# SCH_Stepper-Relay-V2_2024-11-13.net
KiCad netlist of a schematic drawn in EasyEDA
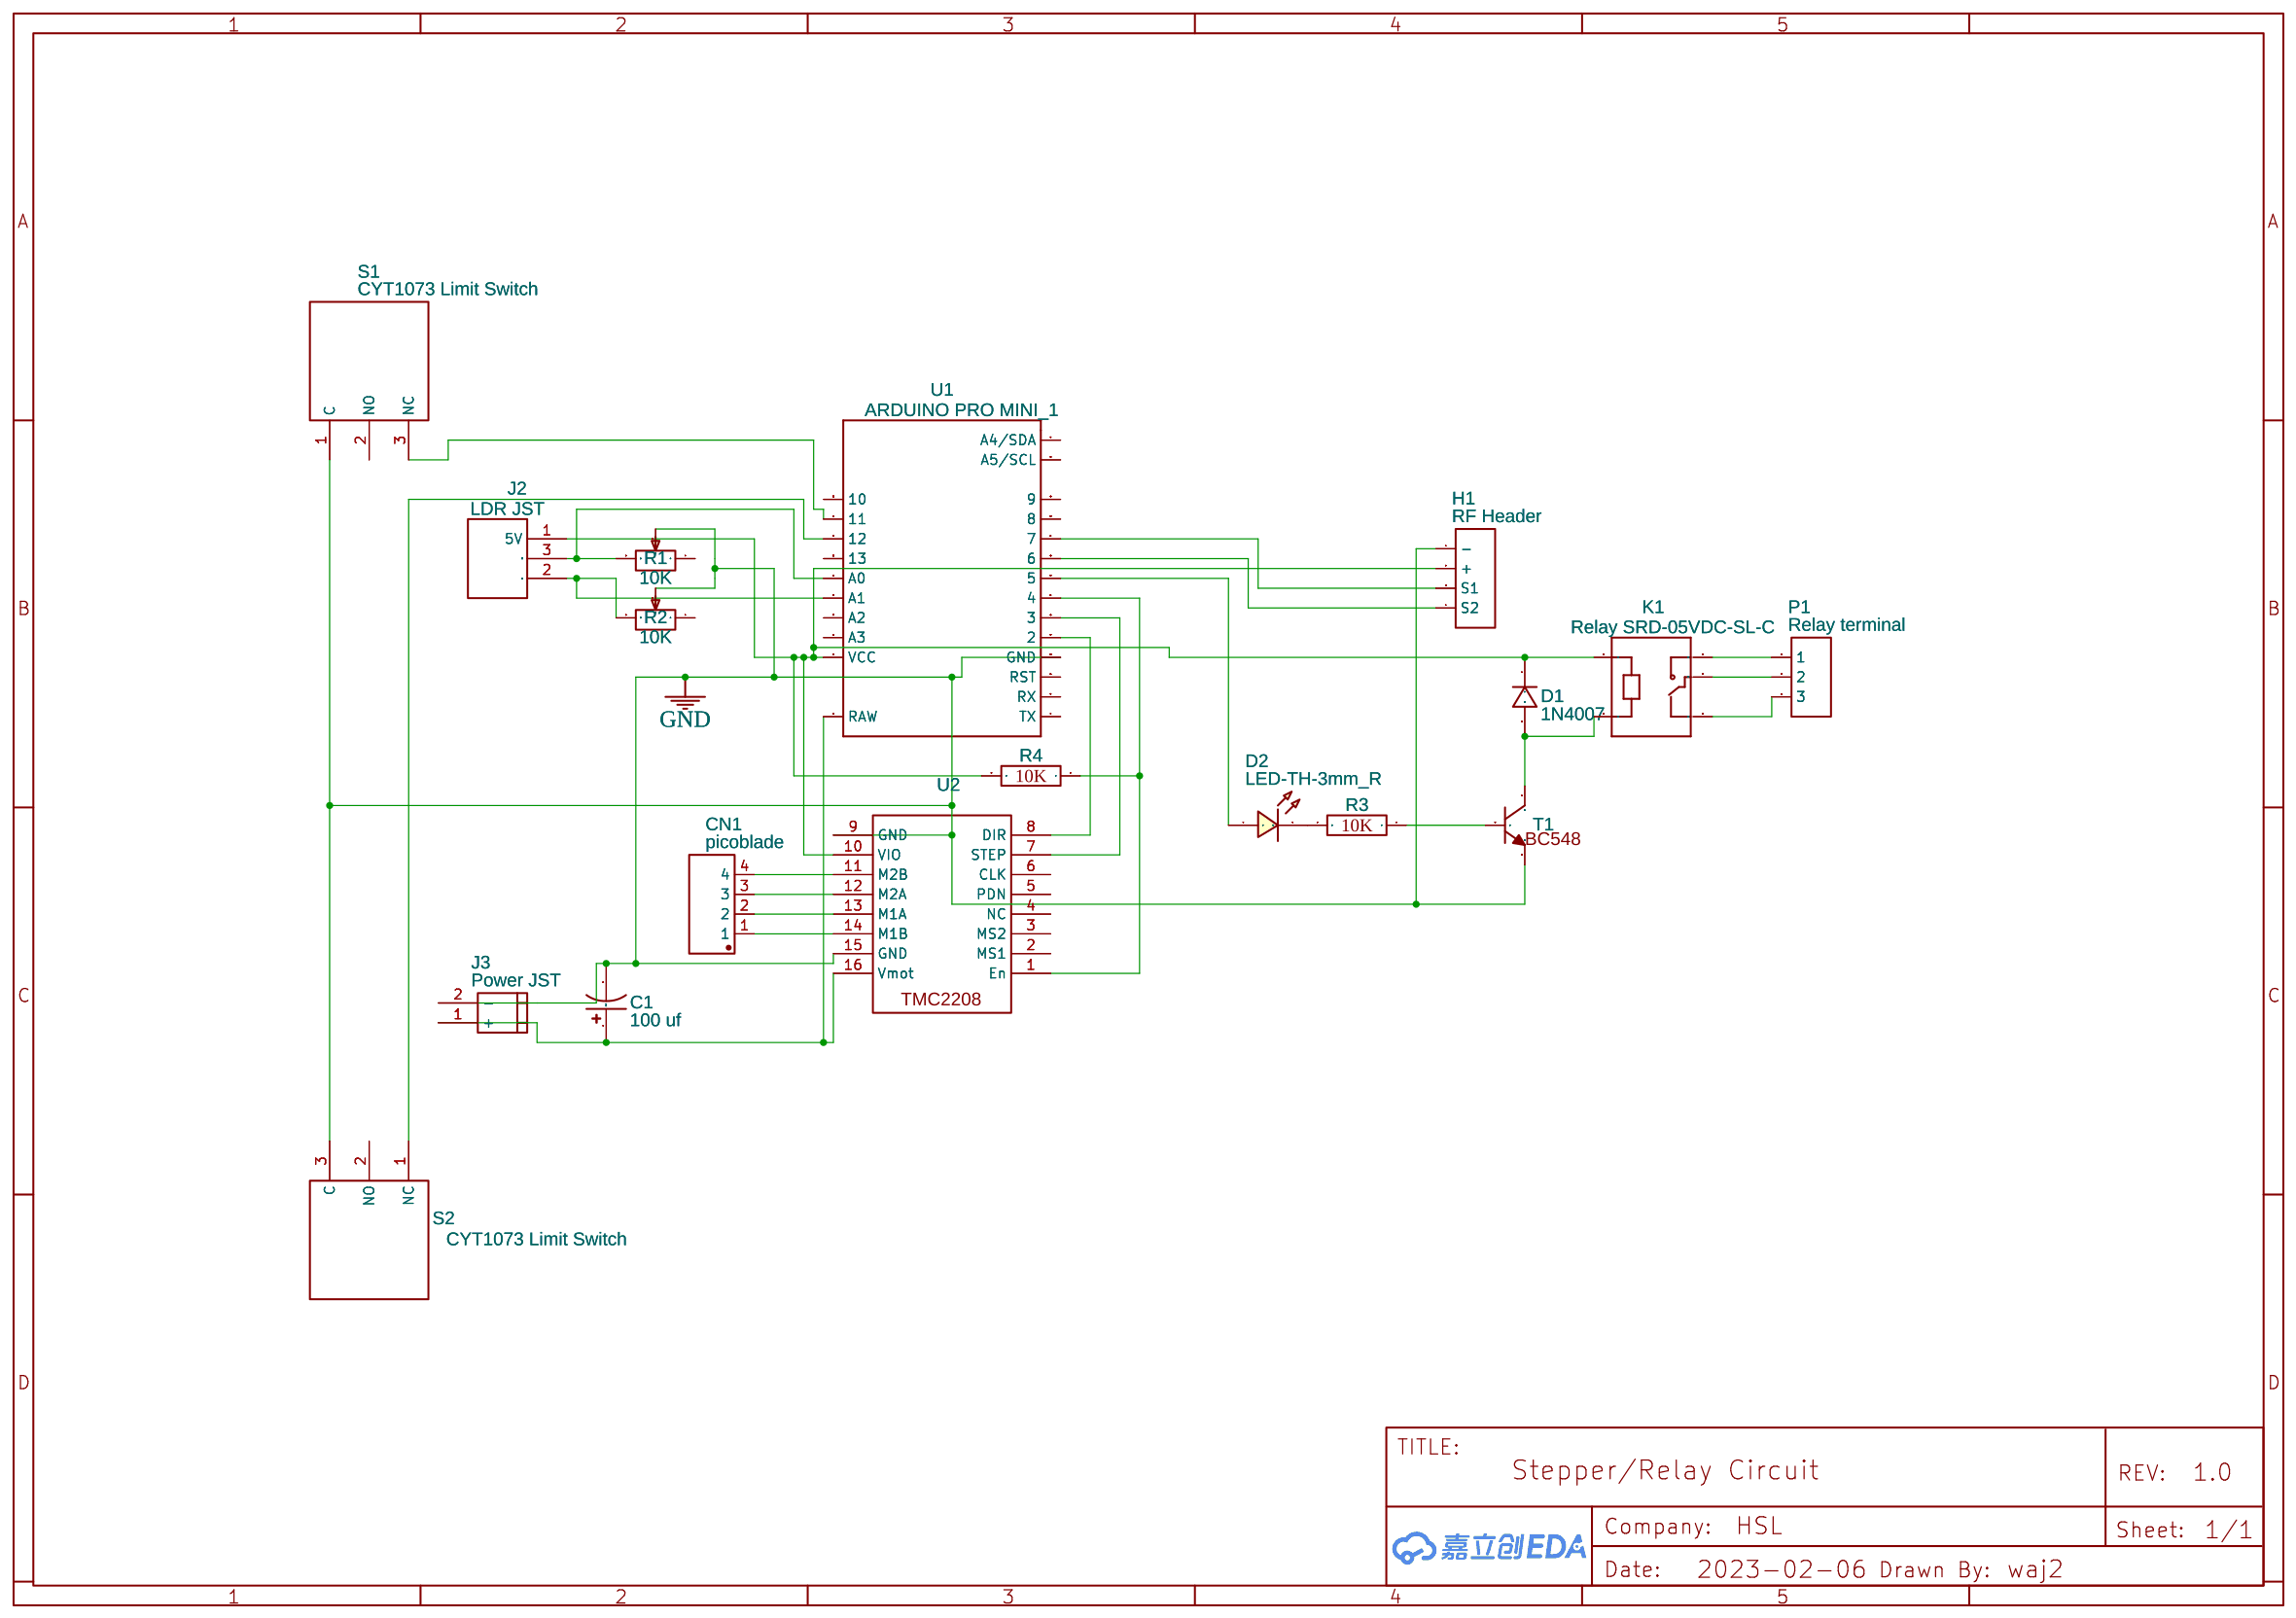
[diagram p0: schematic sheet]

(export (version "E")
  (design (tool "Eeschema 10.0.6"))
  (components
    (comp (ref "C1") (value "100 uf") (libsource (lib "") (part "CE_TH_D6.3×F2.5_US")))
    (comp (ref "CN1")
      (value "picoblade")
      (fields (field (name "Manufacturer Part") "0530474310") (field (name "Manufacturer") "MOLEX"))
      (libsource (lib "") (part "MOLEX_0530470410"))
    )
    (comp (ref "D1")
      (value "1N4007")
      (fields (field (name "Manufacturer") "SEMTECH"))
      (libsource (lib "") (part "1N4007"))
    )
    (comp (ref "D2")
      (value "LED-TH-3mm_R")
      (fields
        (field (name "Manufacturer Part") "204-10SDRD/S530-A3-L")
        (field (name "Manufacturer") "EVERLIGHT(台湾亿光)")
      )
      (libsource (lib "") (part "LED-TH-3mm_R"))
    )
    (comp (ref "H1") (value "RF Header") (libsource (lib "") (part "HDR-F-2.54_1x4")))
    (comp (ref "J2")
      (value "LDR JST")
      (fields (field (name "Manufacturer Part") "JST-5-PTH"))
      (libsource (lib "") (part "JST-HX 3P RIGHT ANGLE COPY"))
    )
    (comp (ref "J3")
      (value "Power JST")
      (fields (field (name "Manufacturer Part") "XH-2PWB") (field (name "Manufacturer") "ReliaPro"))
      (libsource (lib "") (part "XH-2PWB"))
    )
    (comp (ref "K1")
      (value "Relay SRD-05VDC-SL-C")
      (libsource (lib "") (part "SRD-05VDC-SL-C_SRD-05VDC-SL-C"))
    )
    (comp (ref "P1") (value "Relay terminal") (libsource (lib "") (part "CONN-TH_3P-P5.00")))
    (comp (ref "R1")
      (value "10K")
      (fields (field (name "Manufacturer Part") "RM065-V1-5K blue") (field (name "Manufacturer") "ReliaPro"))
      (libsource (lib "") (part "TRIMPOT RM065"))
    )
    (comp (ref "R2")
      (value "10K")
      (fields (field (name "Manufacturer Part") "RM065-V1-5K blue") (field (name "Manufacturer") "ReliaPro"))
      (libsource (lib "") (part "TRIMPOT RM065"))
    )
    (comp (ref "R3") (value "RESISTOR 10K") (libsource (lib "") (part "RESISTOR 10K")))
    (comp (ref "R4") (value "RESISTOR 10K") (libsource (lib "") (part "RESISTOR 10K")))
    (comp (ref "S1")
      (value "CYT1073 Limit Switch")
      (fields (field (name "Manufacturer Part") "Cylewet"))
      (libsource (lib "") (part "CYT1073 Limit Switch"))
    )
    (comp (ref "S2")
      (value "CYT1073 Limit Switch")
      (fields (field (name "Manufacturer Part") "Cylewet"))
      (libsource (lib "") (part "CYT1073 Limit Switch_1"))
    )
    (comp (ref "T1") (value "BC548") (libsource (lib "") (part "BC548")))
    (comp (ref "U1") (value "ARDUINO PRO MINI_1") (libsource (lib "") (part "ARDUINO PRO MINI_1")))
    (comp (ref "U2") (value "U2") (libsource (lib "") (part "ТМС2208v1.0")))
  )
  (nets
    (net (code "1") (name "GND") (class "Default")
      (node (ref "C1") (pin "2") (pinfunction "2_2") (pintype "unspecified"))
      (node (ref "H1") (pin "1") (pinfunction "-_1") (pintype "unspecified"))
      (node (ref "J3") (pin "2") (pinfunction "-_2") (pintype "unspecified"))
      (node (ref "R1") (pin "2") (pinfunction "2_2") (pintype "input"))
      (node (ref "R2") (pin "2") (pinfunction "2_2") (pintype "input"))
      (node (ref "S1") (pin "1") (pinfunction "C_1") (pintype "unspecified"))
      (node (ref "S2") (pin "3") (pinfunction "C_3") (pintype "unspecified"))
      (node (ref "T1") (pin "3") (pinfunction "E_3") (pintype "unspecified"))
      (node (ref "U1") (pin "GND") (pinfunction "GND_GND") (pintype "unspecified"))
      (node (ref "U2") (pin "15") (pinfunction "GND_15") (pintype "unspecified"))
      (node (ref "U2") (pin "9") (pinfunction "GND_9") (pintype "unspecified"))
    )
    (net (code "2") (name "Net-(D2-Pad2)") (class "Default")
      (node (ref "D2") (pin "2") (pinfunction "2_2") (pintype "unspecified"))
      (node (ref "R3") (pin "2") (pinfunction "2_2") (pintype "unspecified"))
    )
    (net (code "3") (name "Net-(H1-+)") (class "Default")
      (node (ref "D1") (pin "1") (pinfunction "1_1") (pintype "unspecified"))
      (node (ref "H1") (pin "2") (pinfunction "+_2") (pintype "unspecified"))
      (node (ref "J2") (pin "1") (pinfunction "5V_1") (pintype "unspecified"))
      (node (ref "K1") (pin "A1") (pinfunction "A1_A1") (pintype "bidirectional"))
      (node (ref "R4") (pin "2") (pinfunction "2_2") (pintype "unspecified"))
      (node (ref "U1") (pin "VCC") (pinfunction "VCC_VCC") (pintype "unspecified"))
      (node (ref "U2") (pin "10") (pinfunction "VIO_10") (pintype "unspecified"))
    )
    (net (code "4") (name "Net-(H1-S1)") (class "Default")
      (node (ref "H1") (pin "3") (pinfunction "S1_3") (pintype "unspecified"))
      (node (ref "U1") (pin "D7") (pinfunction "7_D7") (pintype "unspecified"))
    )
    (net (code "5") (name "Net-(H1-S2)") (class "Default")
      (node (ref "H1") (pin "4") (pinfunction "S2_4") (pintype "unspecified"))
      (node (ref "U1") (pin "D6") (pinfunction "6_D6") (pintype "unspecified"))
    )
    (net (code "6") (name "Net-(J2-S1)") (class "Default")
      (node (ref "J2") (pin "2") (pinfunction "S1_2") (pintype "unspecified"))
      (node (ref "R2") (pin "3") (pinfunction "3_3") (pintype "input"))
      (node (ref "U1") (pin "A1") (pinfunction "A1_A1") (pintype "unspecified"))
    )
    (net (code "7") (name "Net-(J2-S2)") (class "Default")
      (node (ref "J2") (pin "3") (pinfunction "S2_3") (pintype "unspecified"))
      (node (ref "R1") (pin "3") (pinfunction "3_3") (pintype "input"))
      (node (ref "U1") (pin "A0") (pinfunction "A0_A0") (pintype "unspecified"))
    )
    (net (code "8") (name "Net-(J3-+)") (class "Default")
      (node (ref "C1") (pin "1") (pinfunction "1_1") (pintype "unspecified"))
      (node (ref "J3") (pin "1") (pinfunction "+_1") (pintype "unspecified"))
      (node (ref "U1") (pin "RAW") (pinfunction "RAW_RAW") (pintype "unspecified"))
      (node (ref "U2") (pin "16") (pinfunction "Vmot_16") (pintype "unspecified"))
    )
    (net (code "9") (name "Net-(K1-PadCOM)") (class "Default")
      (node (ref "K1") (pin "COM") (pinfunction "COM_COM") (pintype "bidirectional"))
      (node (ref "P1") (pin "2") (pinfunction "2_2") (pintype "unspecified"))
    )
    (net (code "10") (name "Net-(K1-PadNC)") (class "Default")
      (node (ref "K1") (pin "NC") (pinfunction "NC_NC") (pintype "bidirectional"))
      (node (ref "P1") (pin "3") (pinfunction "3_3") (pintype "unspecified"))
    )
    (net (code "11") (name "Net-(K1-PadNO)") (class "Default")
      (node (ref "K1") (pin "NO") (pinfunction "NO_NO") (pintype "bidirectional"))
      (node (ref "P1") (pin "1") (pinfunction "1_1") (pintype "unspecified"))
    )
    (net (code "12") (name "Net-(S1-NC)") (class "Default")
      (node (ref "S1") (pin "3") (pinfunction "NC_3") (pintype "unspecified"))
      (node (ref "U1") (pin "D11") (pinfunction "11_D11") (pintype "unspecified"))
    )
    (net (code "13") (name "Net-(S2-NC)") (class "Default")
      (node (ref "S2") (pin "1") (pinfunction "NC_1") (pintype "unspecified"))
      (node (ref "U1") (pin "D12") (pinfunction "12_D12") (pintype "unspecified"))
    )
    (net (code "14") (name "Net-(T1-B)") (class "Default")
      (node (ref "R3") (pin "1") (pinfunction "1_1") (pintype "unspecified"))
      (node (ref "T1") (pin "2") (pinfunction "B_2") (pintype "unspecified"))
    )
    (net (code "15") (name "Net-(T1-C)") (class "Default")
      (node (ref "D1") (pin "2") (pinfunction "2_2") (pintype "unspecified"))
      (node (ref "K1") (pin "A2") (pinfunction "A2_A2") (pintype "bidirectional"))
      (node (ref "T1") (pin "1") (pinfunction "C_1") (pintype "unspecified"))
    )
    (net (code "16") (name "Net-(U1-2)") (class "Default")
      (node (ref "U1") (pin "D2") (pinfunction "2_D2") (pintype "unspecified"))
      (node (ref "U2") (pin "8") (pinfunction "DIR_8") (pintype "unspecified"))
    )
    (net (code "17") (name "Net-(U1-3)") (class "Default")
      (node (ref "U1") (pin "D3") (pinfunction "3_D3") (pintype "unspecified"))
      (node (ref "U2") (pin "7") (pinfunction "STEP_7") (pintype "unspecified"))
    )
    (net (code "18") (name "Net-(U1-4)") (class "Default")
      (node (ref "R4") (pin "1") (pinfunction "1_1") (pintype "unspecified"))
      (node (ref "U1") (pin "D4") (pinfunction "4_D4") (pintype "unspecified"))
      (node (ref "U2") (pin "1") (pinfunction "En_1") (pintype "unspecified"))
    )
    (net (code "19") (name "Net-(U1-5)") (class "Default")
      (node (ref "D2") (pin "1") (pinfunction "1_1") (pintype "unspecified"))
      (node (ref "U1") (pin "D5") (pinfunction "5_D5") (pintype "unspecified"))
    )
    (net (code "20") (name "Net-(U2-M1A)") (class "Default")
      (node (ref "CN1") (pin "2") (pinfunction "2_2") (pintype "unspecified"))
      (node (ref "U2") (pin "13") (pinfunction "M1A_13") (pintype "unspecified"))
    )
    (net (code "21") (name "Net-(U2-M1B)") (class "Default")
      (node (ref "CN1") (pin "1") (pinfunction "1_1") (pintype "unspecified"))
      (node (ref "U2") (pin "14") (pinfunction "M1B_14") (pintype "unspecified"))
    )
    (net (code "22") (name "Net-(U2-M2A)") (class "Default")
      (node (ref "CN1") (pin "3") (pinfunction "3_3") (pintype "unspecified"))
      (node (ref "U2") (pin "12") (pinfunction "M2A_12") (pintype "unspecified"))
    )
    (net (code "23") (name "Net-(U2-M2B)") (class "Default")
      (node (ref "CN1") (pin "4") (pinfunction "4_4") (pintype "unspecified"))
      (node (ref "U2") (pin "11") (pinfunction "M2B_11") (pintype "unspecified"))
    )
    (net (code "24") (name "unconnected-(R1-Pad1)") (class "Default")
      (node (ref "R1") (pin "1") (pinfunction "1_1") (pintype "input"))
    )
    (net (code "25") (name "unconnected-(R2-Pad1)") (class "Default")
      (node (ref "R2") (pin "1") (pinfunction "1_1") (pintype "input"))
    )
    (net (code "26") (name "unconnected-(S1-NO-Pad2)") (class "Default")
      (node (ref "S1") (pin "2") (pinfunction "NO_2") (pintype "unspecified"))
    )
    (net (code "27") (name "unconnected-(S2-NO-Pad2)") (class "Default")
      (node (ref "S2") (pin "2") (pinfunction "NO_2") (pintype "unspecified"))
    )
    (net (code "28") (name "unconnected-(U1-8-PadD8)") (class "Default")
      (node (ref "U1") (pin "D8") (pinfunction "8_D8") (pintype "unspecified"))
    )
    (net (code "29") (name "unconnected-(U1-9-PadD9)") (class "Default")
      (node (ref "U1") (pin "D9") (pinfunction "9_D9") (pintype "unspecified"))
    )
    (net (code "30") (name "unconnected-(U1-10-PadD10)") (class "Default")
      (node (ref "U1") (pin "D10") (pinfunction "10_D10") (pintype "unspecified"))
    )
    (net (code "31") (name "unconnected-(U1-13-PadD13)") (class "Default")
      (node (ref "U1") (pin "D13") (pinfunction "13_D13") (pintype "unspecified"))
    )
    (net (code "32") (name "unconnected-(U1-A4{slash}SDA-PadA4)") (class "Default")
      (node (ref "U1") (pin "A4") (pinfunction "A4/SDA_A4") (pintype "unspecified"))
    )
    (net (code "33") (name "unconnected-(U1-A5{slash}SCL-PadA5)") (class "Default")
      (node (ref "U1") (pin "A5") (pinfunction "A5/SCL_A5") (pintype "unspecified"))
    )
    (net (code "34") (name "unconnected-(U1-PadA2)") (class "Default")
      (node (ref "U1") (pin "A2") (pinfunction "A2_A2") (pintype "unspecified"))
    )
    (net (code "35") (name "unconnected-(U1-PadA3)") (class "Default")
      (node (ref "U1") (pin "A3") (pinfunction "A3_A3") (pintype "unspecified"))
    )
    (net (code "36") (name "unconnected-(U1-PadRST)") (class "Default")
      (node (ref "U1") (pin "RST") (pinfunction "RST_RST") (pintype "unspecified"))
    )
    (net (code "37") (name "unconnected-(U1-PadRX)") (class "Default")
      (node (ref "U1") (pin "RX") (pinfunction "RX_RX") (pintype "unspecified"))
    )
    (net (code "38") (name "unconnected-(U1-PadTX)") (class "Default")
      (node (ref "U1") (pin "TX") (pinfunction "TX_TX") (pintype "unspecified"))
    )
    (net (code "39") (name "unconnected-(U2-CLK-Pad6)") (class "Default")
      (node (ref "U2") (pin "6") (pinfunction "CLK_6") (pintype "unspecified"))
    )
    (net (code "40") (name "unconnected-(U2-MS1-Pad2)") (class "Default")
      (node (ref "U2") (pin "2") (pinfunction "MS1_2") (pintype "unspecified"))
    )
    (net (code "41") (name "unconnected-(U2-MS2-Pad3)") (class "Default")
      (node (ref "U2") (pin "3") (pinfunction "MS2_3") (pintype "unspecified"))
    )
    (net (code "42") (name "unconnected-(U2-NC-Pad4)") (class "Default")
      (node (ref "U2") (pin "4") (pinfunction "NC_4") (pintype "unspecified"))
    )
    (net (code "43") (name "unconnected-(U2-PDN-Pad5)") (class "Default")
      (node (ref "U2") (pin "5") (pinfunction "PDN_5") (pintype "unspecified"))
    )
  )
)
